# 6M4HzClock.net
KiCad netlist of a schematic drawn in EAGLE
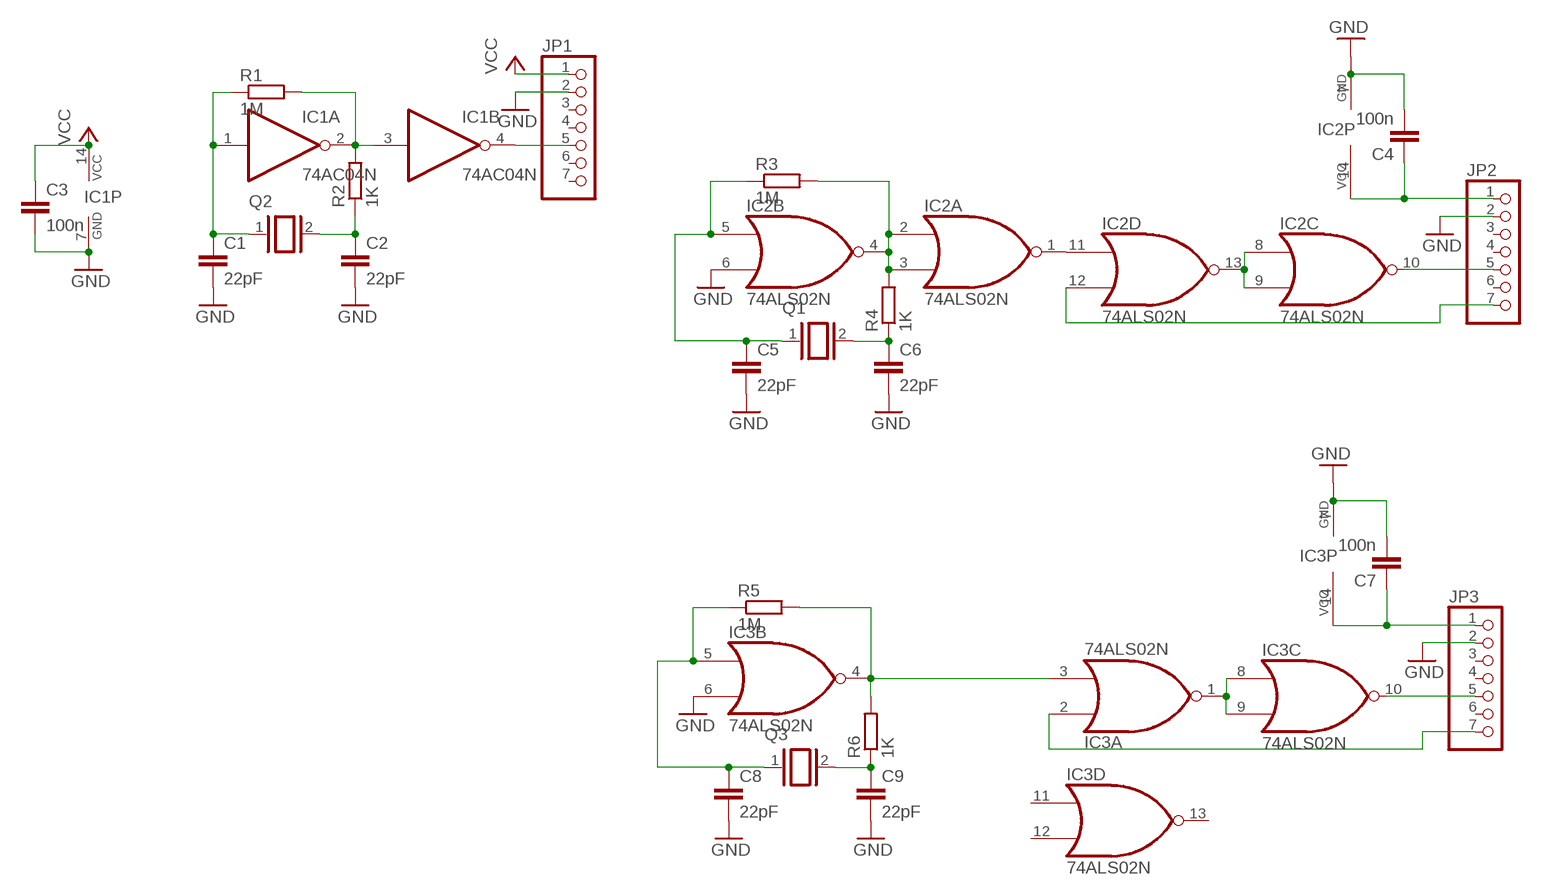
[diagram p0: schematic, sheet 1]

(export (version "E")
  (design (tool "Eeschema 10.0.6"))
  (components
    (comp (ref "C1")
      (value "22pF")
      (footprint "eagle-import:C025-024X044")
      (libsource (lib "eagle-import") (part "C-EU025-024X044"))
    )
    (comp (ref "C2")
      (value "22pF")
      (footprint "eagle-import:C025-024X044")
      (libsource (lib "eagle-import") (part "C-EU025-024X044"))
    )
    (comp (ref "C3")
      (value "100n")
      (footprint "eagle-import:C050-024X044")
      (libsource (lib "eagle-import") (part "C-EU050-024X044"))
    )
    (comp (ref "C4")
      (value "100n")
      (footprint "eagle-import:C050-024X044")
      (libsource (lib "eagle-import") (part "C-EU050-024X044"))
    )
    (comp (ref "C5")
      (value "22pF")
      (footprint "eagle-import:C025-024X044")
      (libsource (lib "eagle-import") (part "C-EU025-024X044"))
    )
    (comp (ref "C6")
      (value "22pF")
      (footprint "eagle-import:C025-024X044")
      (libsource (lib "eagle-import") (part "C-EU025-024X044"))
    )
    (comp (ref "C7")
      (value "100n")
      (footprint "eagle-import:C050-024X044")
      (libsource (lib "eagle-import") (part "C-EU050-024X044"))
    )
    (comp (ref "C8")
      (value "22pF")
      (footprint "eagle-import:C025-024X044")
      (libsource (lib "eagle-import") (part "C-EU025-024X044"))
    )
    (comp (ref "C9")
      (value "22pF")
      (footprint "eagle-import:C025-024X044")
      (libsource (lib "eagle-import") (part "C-EU025-024X044"))
    )
    (comp (ref "IC1")
      (value "74AC04N")
      (footprint "eagle-import:DIL14")
      (libsource (lib "eagle-import") (part "7404NAC"))
    )
    (comp (ref "IC2")
      (value "74ALS02N")
      (footprint "eagle-import:DIL14")
      (libsource (lib "eagle-import") (part "7402NALS"))
    )
    (comp (ref "IC3")
      (value "74ALS02N")
      (footprint "eagle-import:DIL14")
      (libsource (lib "eagle-import") (part "7402NALS"))
    )
    (comp (ref "JP1")
      (value "PINHD-1X7")
      (footprint "eagle-import:1X07")
      (libsource (lib "eagle-import") (part "PINHD-1X7"))
    )
    (comp (ref "JP2")
      (value "PINHD-1X7")
      (footprint "eagle-import:1X07")
      (libsource (lib "eagle-import") (part "PINHD-1X7"))
    )
    (comp (ref "JP3")
      (value "PINHD-1X7")
      (footprint "eagle-import:1X07")
      (libsource (lib "eagle-import") (part "PINHD-1X7"))
    )
    (comp (ref "Q1")
      (value "XTAL/S")
      (footprint "eagle-import:QS")
      (libsource (lib "eagle-import") (part "XTAL/S"))
    )
    (comp (ref "Q2")
      (value "XTAL/S")
      (footprint "eagle-import:QS")
      (libsource (lib "eagle-import") (part "XTAL/S"))
    )
    (comp (ref "Q3")
      (value "XTAL/S")
      (footprint "eagle-import:QS")
      (libsource (lib "eagle-import") (part "XTAL/S"))
    )
    (comp (ref "R1")
      (value "1M")
      (footprint "eagle-import:0204V")
      (libsource (lib "eagle-import") (part "R-EU_0204/2V"))
    )
    (comp (ref "R2")
      (value "1K")
      (footprint "eagle-import:0204V")
      (libsource (lib "eagle-import") (part "R-EU_0204/2V"))
    )
    (comp (ref "R3")
      (value "1M")
      (footprint "eagle-import:0204V")
      (libsource (lib "eagle-import") (part "R-EU_0204/2V"))
    )
    (comp (ref "R4")
      (value "1K")
      (footprint "eagle-import:0204V")
      (libsource (lib "eagle-import") (part "R-EU_0204/2V"))
    )
    (comp (ref "R5")
      (value "1M")
      (footprint "eagle-import:0204V")
      (libsource (lib "eagle-import") (part "R-EU_0204/2V"))
    )
    (comp (ref "R6")
      (value "1K")
      (footprint "eagle-import:0204V")
      (libsource (lib "eagle-import") (part "R-EU_0204/2V"))
    )
  )
  (nets
    (net (code "1") (name "/6.4MHZ{slash}OUT") (class "Default")
      (node (ref "IC2") (pin "10") (pinfunction "O_10") (pintype "output"))
      (node (ref "JP2") (pin "5") (pinfunction "5_5") (pintype "passive"))
    )
    (net (code "2") (name "/6.4MHZ{slash}OUT1") (class "Default")
      (node (ref "IC3") (pin "10") (pinfunction "O_10") (pintype "output"))
      (node (ref "JP3") (pin "5") (pinfunction "5_5") (pintype "passive"))
    )
    (net (code "3") (name "GND") (class "Default")
      (node (ref "C1") (pin "2") (pinfunction "2_2") (pintype "passive"))
      (node (ref "C2") (pin "2") (pinfunction "2_2") (pintype "passive"))
      (node (ref "C3") (pin "2") (pinfunction "2_2") (pintype "passive"))
      (node (ref "C5") (pin "2") (pinfunction "2_2") (pintype "passive"))
      (node (ref "C6") (pin "2") (pinfunction "2_2") (pintype "passive"))
      (node (ref "C8") (pin "2") (pinfunction "2_2") (pintype "passive"))
      (node (ref "C9") (pin "2") (pinfunction "2_2") (pintype "passive"))
      (node (ref "IC1") (pin "7") (pinfunction "GND_7") (pintype "power_in"))
      (node (ref "IC2") (pin "6") (pinfunction "I1_6") (pintype "input"))
      (node (ref "IC2") (pin "7") (pinfunction "GND_7") (pintype "power_in"))
      (node (ref "IC3") (pin "6") (pinfunction "I1_6") (pintype "input"))
      (node (ref "IC3") (pin "7") (pinfunction "GND_7") (pintype "power_in"))
      (node (ref "JP1") (pin "2") (pinfunction "2_2") (pintype "passive"))
      (node (ref "JP2") (pin "2") (pinfunction "2_2") (pintype "passive"))
      (node (ref "JP3") (pin "2") (pinfunction "2_2") (pintype "passive"))
    )
    (net (code "4") (name "Net-(C2-Pad1)") (class "Default")
      (node (ref "C2") (pin "1") (pinfunction "1_1") (pintype "passive"))
      (node (ref "Q2") (pin "2") (pinfunction "2_2") (pintype "passive"))
      (node (ref "R2") (pin "1") (pinfunction "1_1") (pintype "passive"))
    )
    (net (code "5") (name "Net-(C6-Pad1)") (class "Default")
      (node (ref "C6") (pin "1") (pinfunction "1_1") (pintype "passive"))
      (node (ref "Q1") (pin "2") (pinfunction "2_2") (pintype "passive"))
      (node (ref "R4") (pin "1") (pinfunction "1_1") (pintype "passive"))
    )
    (net (code "6") (name "Net-(C9-Pad1)") (class "Default")
      (node (ref "C9") (pin "1") (pinfunction "1_1") (pintype "passive"))
      (node (ref "Q3") (pin "2") (pinfunction "2_2") (pintype "passive"))
      (node (ref "R6") (pin "1") (pinfunction "1_1") (pintype "passive"))
    )
    (net (code "7") (name "Net-(IC1A-I)") (class "Default")
      (node (ref "C1") (pin "1") (pinfunction "1_1") (pintype "passive"))
      (node (ref "IC1") (pin "1") (pinfunction "I_1") (pintype "input"))
      (node (ref "Q2") (pin "1") (pinfunction "1_1") (pintype "passive"))
      (node (ref "R1") (pin "1") (pinfunction "1_1") (pintype "passive"))
    )
    (net (code "8") (name "Net-(IC1A-O)") (class "Default")
      (node (ref "IC1") (pin "2") (pinfunction "O_2") (pintype "output"))
      (node (ref "IC1") (pin "3") (pinfunction "I_3") (pintype "input"))
      (node (ref "R1") (pin "2") (pinfunction "2_2") (pintype "passive"))
      (node (ref "R2") (pin "2") (pinfunction "2_2") (pintype "passive"))
    )
    (net (code "9") (name "Net-(IC1B-O)") (class "Default")
      (node (ref "IC1") (pin "4") (pinfunction "O_4") (pintype "output"))
      (node (ref "JP1") (pin "5") (pinfunction "5_5") (pintype "passive"))
    )
    (net (code "10") (name "Net-(IC2A-I0)") (class "Default")
      (node (ref "IC2") (pin "2") (pinfunction "I0_2") (pintype "input"))
      (node (ref "IC2") (pin "3") (pinfunction "I1_3") (pintype "input"))
      (node (ref "IC2") (pin "4") (pinfunction "O_4") (pintype "output"))
      (node (ref "R3") (pin "2") (pinfunction "2_2") (pintype "passive"))
      (node (ref "R4") (pin "2") (pinfunction "2_2") (pintype "passive"))
    )
    (net (code "11") (name "Net-(IC2A-O)") (class "Default")
      (node (ref "IC2") (pin "1") (pinfunction "O_1") (pintype "output"))
      (node (ref "IC2") (pin "11") (pinfunction "I0_11") (pintype "input"))
    )
    (net (code "12") (name "Net-(IC2B-I0)") (class "Default")
      (node (ref "C5") (pin "1") (pinfunction "1_1") (pintype "passive"))
      (node (ref "IC2") (pin "5") (pinfunction "I0_5") (pintype "input"))
      (node (ref "Q1") (pin "1") (pinfunction "1_1") (pintype "passive"))
      (node (ref "R3") (pin "1") (pinfunction "1_1") (pintype "passive"))
    )
    (net (code "13") (name "Net-(IC2C-I0)") (class "Default")
      (node (ref "IC2") (pin "13") (pinfunction "O_13") (pintype "output"))
      (node (ref "IC2") (pin "8") (pinfunction "I0_8") (pintype "input"))
      (node (ref "IC2") (pin "9") (pinfunction "I1_9") (pintype "input"))
    )
    (net (code "14") (name "Net-(IC2D-I1)") (class "Default")
      (node (ref "IC2") (pin "12") (pinfunction "I1_12") (pintype "input"))
      (node (ref "JP2") (pin "7") (pinfunction "7_7") (pintype "passive"))
    )
    (net (code "15") (name "Net-(IC2E-VCC)") (class "Default")
      (node (ref "C4") (pin "1") (pinfunction "1_1") (pintype "passive"))
      (node (ref "IC2") (pin "14") (pinfunction "VCC_14") (pintype "power_in"))
      (node (ref "JP2") (pin "1") (pinfunction "1_1") (pintype "passive"))
    )
    (net (code "16") (name "Net-(IC3A-I0)") (class "Default")
      (node (ref "IC3") (pin "2") (pinfunction "I0_2") (pintype "input"))
      (node (ref "JP3") (pin "7") (pinfunction "7_7") (pintype "passive"))
    )
    (net (code "17") (name "Net-(IC3A-I1)") (class "Default")
      (node (ref "IC3") (pin "3") (pinfunction "I1_3") (pintype "input"))
      (node (ref "IC3") (pin "4") (pinfunction "O_4") (pintype "output"))
      (node (ref "R5") (pin "2") (pinfunction "2_2") (pintype "passive"))
      (node (ref "R6") (pin "2") (pinfunction "2_2") (pintype "passive"))
    )
    (net (code "18") (name "Net-(IC3A-O)") (class "Default")
      (node (ref "IC3") (pin "1") (pinfunction "O_1") (pintype "output"))
      (node (ref "IC3") (pin "8") (pinfunction "I0_8") (pintype "input"))
      (node (ref "IC3") (pin "9") (pinfunction "I1_9") (pintype "input"))
    )
    (net (code "19") (name "Net-(IC3B-I0)") (class "Default")
      (node (ref "C8") (pin "1") (pinfunction "1_1") (pintype "passive"))
      (node (ref "IC3") (pin "5") (pinfunction "I0_5") (pintype "input"))
      (node (ref "Q3") (pin "1") (pinfunction "1_1") (pintype "passive"))
      (node (ref "R5") (pin "1") (pinfunction "1_1") (pintype "passive"))
    )
    (net (code "20") (name "Net-(IC3E-VCC)") (class "Default")
      (node (ref "C7") (pin "1") (pinfunction "1_1") (pintype "passive"))
      (node (ref "IC3") (pin "14") (pinfunction "VCC_14") (pintype "power_in"))
      (node (ref "JP3") (pin "1") (pinfunction "1_1") (pintype "passive"))
    )
    (net (code "21") (name "VCC") (class "Default")
      (node (ref "C3") (pin "1") (pinfunction "1_1") (pintype "passive"))
      (node (ref "IC1") (pin "14") (pinfunction "VCC_14") (pintype "power_in"))
      (node (ref "JP1") (pin "1") (pinfunction "1_1") (pintype "passive"))
    )
    (net (code "22") (name "unconnected-(C4-Pad2)") (class "Default")
      (node (ref "C4") (pin "2") (pinfunction "2_2") (pintype "passive"))
    )
    (net (code "23") (name "unconnected-(C7-Pad2)") (class "Default")
      (node (ref "C7") (pin "2") (pinfunction "2_2") (pintype "passive"))
    )
    (net (code "24") (name "unconnected-(IC3D-I0-Pad11)") (class "Default")
      (node (ref "IC3") (pin "11") (pinfunction "I0_11") (pintype "input"))
    )
    (net (code "25") (name "unconnected-(IC3D-I1-Pad12)") (class "Default")
      (node (ref "IC3") (pin "12") (pinfunction "I1_12") (pintype "input"))
    )
    (net (code "26") (name "unconnected-(IC3D-O-Pad13)") (class "Default")
      (node (ref "IC3") (pin "13") (pinfunction "O_13") (pintype "output"))
    )
    (net (code "27") (name "unconnected-(JP1-Pad3)") (class "Default")
      (node (ref "JP1") (pin "3") (pinfunction "3_3") (pintype "passive"))
    )
    (net (code "28") (name "unconnected-(JP1-Pad4)") (class "Default")
      (node (ref "JP1") (pin "4") (pinfunction "4_4") (pintype "passive"))
    )
    (net (code "29") (name "unconnected-(JP1-Pad6)") (class "Default")
      (node (ref "JP1") (pin "6") (pinfunction "6_6") (pintype "passive"))
    )
    (net (code "30") (name "unconnected-(JP1-Pad7)") (class "Default")
      (node (ref "JP1") (pin "7") (pinfunction "7_7") (pintype "passive"))
    )
    (net (code "31") (name "unconnected-(JP2-Pad3)") (class "Default")
      (node (ref "JP2") (pin "3") (pinfunction "3_3") (pintype "passive"))
    )
    (net (code "32") (name "unconnected-(JP2-Pad4)") (class "Default")
      (node (ref "JP2") (pin "4") (pinfunction "4_4") (pintype "passive"))
    )
    (net (code "33") (name "unconnected-(JP2-Pad6)") (class "Default")
      (node (ref "JP2") (pin "6") (pinfunction "6_6") (pintype "passive"))
    )
    (net (code "34") (name "unconnected-(JP3-Pad3)") (class "Default")
      (node (ref "JP3") (pin "3") (pinfunction "3_3") (pintype "passive"))
    )
    (net (code "35") (name "unconnected-(JP3-Pad4)") (class "Default")
      (node (ref "JP3") (pin "4") (pinfunction "4_4") (pintype "passive"))
    )
    (net (code "36") (name "unconnected-(JP3-Pad6)") (class "Default")
      (node (ref "JP3") (pin "6") (pinfunction "6_6") (pintype "passive"))
    )
  )
)
